# POWER_SUPPLY.net
KiCad netlist of a schematic drawn in Altium Designer
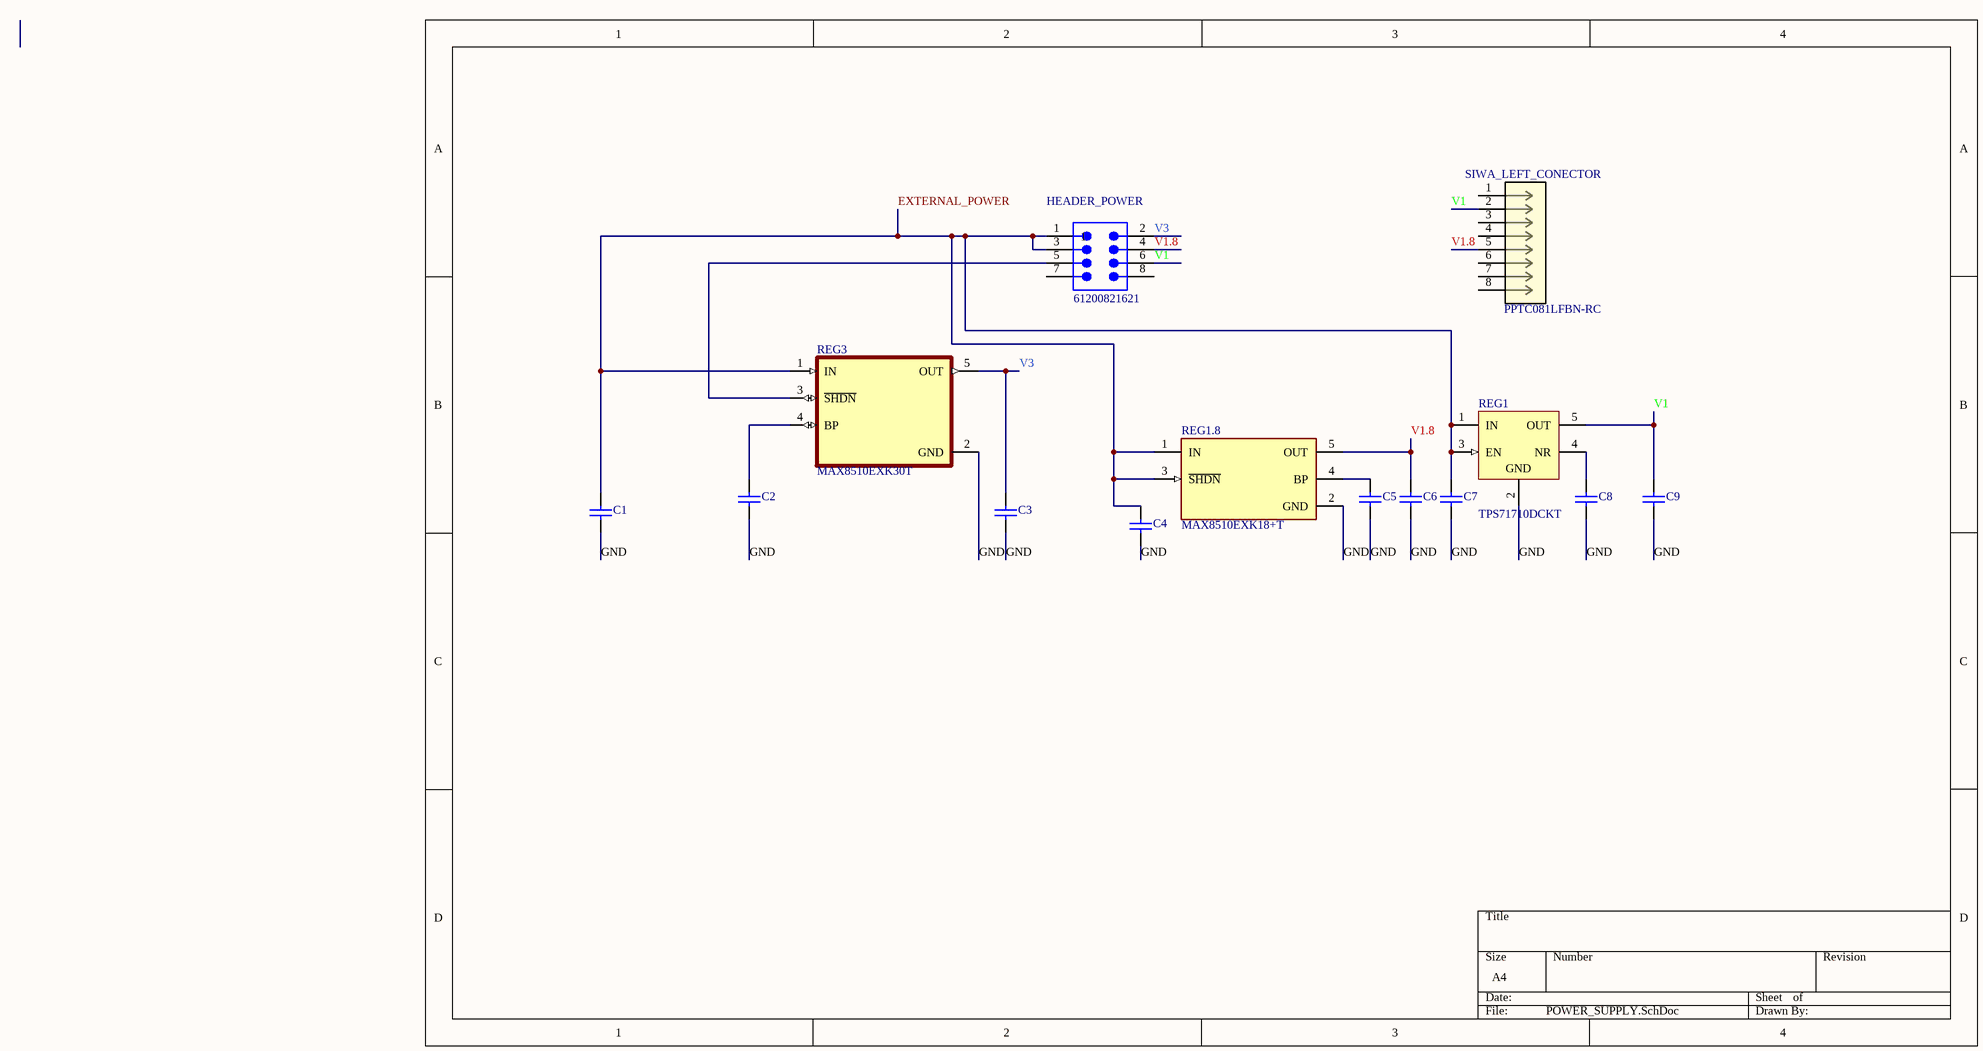
[diagram p0: POWER_SUPPLY.SchDoc]

(export (version "E")
  (design (tool "Eeschema 10.0.6"))
  (components
    (comp (ref "C1")
      (value "VJ0603Y102KXJAC")
      (footprint "CAPC1608X92X38ML15T08")
      (fields (field (name "MANUFACTURER") "Vitramon"))
      (libsource (lib "Altium Content Vault") (part "CAP"))
    )
    (comp (ref "C2")
      (value "VJ0603Y102KXJAC")
      (footprint "CAPC1608X92X38ML15T08")
      (fields (field (name "MANUFACTURER") "Vitramon"))
      (libsource (lib "Altium Content Vault") (part "CAP"))
    )
    (comp (ref "C3")
      (value "VJ0603Y102KXJAC")
      (footprint "CAPC1608X92X38ML15T08")
      (fields (field (name "MANUFACTURER") "Vitramon"))
      (libsource (lib "Altium Content Vault") (part "CAP"))
    )
    (comp (ref "C4")
      (value "VJ0603Y102KXJAC")
      (footprint "CAPC1608X92X38ML15T08")
      (fields (field (name "MANUFACTURER") "Vitramon"))
      (libsource (lib "Altium Content Vault") (part "CAP"))
    )
    (comp (ref "C5")
      (value "VJ0603Y102KXJAC")
      (footprint "CAPC1608X92X38ML15T08")
      (fields (field (name "MANUFACTURER") "Vitramon"))
      (libsource (lib "Altium Content Vault") (part "CAP"))
    )
    (comp (ref "C6")
      (value "VJ0603Y102KXJAC")
      (footprint "CAPC1608X92X38ML15T08")
      (fields (field (name "MANUFACTURER") "Vitramon"))
      (libsource (lib "Altium Content Vault") (part "CAP"))
    )
    (comp (ref "C7")
      (value "VJ0603Y102KXJAC")
      (footprint "CAPC1608X92X38ML15T08")
      (fields (field (name "MANUFACTURER") "Vitramon"))
      (libsource (lib "Altium Content Vault") (part "CAP"))
    )
    (comp (ref "C8")
      (value "VJ0603Y102KXJAC")
      (footprint "CAPC1608X92X38ML15T08")
      (fields (field (name "MANUFACTURER") "Vitramon"))
      (libsource (lib "Altium Content Vault") (part "CAP"))
    )
    (comp (ref "C9")
      (value "VJ0603Y102KXJAC")
      (footprint "CAPC1608X92X38ML15T08")
      (fields (field (name "MANUFACTURER") "Vitramon"))
      (libsource (lib "Altium Content Vault") (part "CAP"))
    )
    (comp (ref "HEADER_POWER")
      (value "61200821621")
      (footprint "61200821621")
      (description "Wr-bhd; 2.54MM Pitch 8 Way 2 Row Shrouded Straight Pcb Header, Surface Mount")
      (libsource (lib "Altium Content Vault") (part "Header_Male_2R_08P"))
    )
    (comp (ref "REG1")
      (value "TPS71710DCKT")
      (footprint "DCK0005A_M")
      (fields (field (name "MANUFACTURER") "Texas Instruments"))
      (libsource (lib "Altium Content Vault") (part "TI-TPS79NXX-YYSOT5"))
    )
    (comp (ref "REG1.8")
      (value "MAX8510EXK18+T")
      (footprint "FP-X5-1-MFG")
      (description "IC REG LINEAR 1.8V 120MA SC70-5")
      (libsource (lib "Altium Content Vault") (part "355d6218c957986cfc1b3588039a240"))
    )
    (comp (ref "REG3")
      (value "MAX8510EXK30T")
      (footprint "SOT65P210X110-5N")
      (description "DoÄŸrusal Voltaj RegÃ¼latÃ¶rÃ¼ IC Pozitif Sabit 1 Ã‡Ä±kÄ±ÅŸ 120mA SC-70-5")
      (fields (field (name "MF") "Maxim Integrated Products") (field (name "MP") "MAX8510EXK30+T"))
      (libsource (lib "MAX8510EXK30T") (part "MAX8510EXK30T"))
    )
    (comp (ref "SIWA_LEFT_CONECTOR")
      (value "PPTC081LFBN-RC")
      (footprint "CONN_PPTC081LFBN-RC_SUL")
      (description "Description")
      (fields (field (name "COPYRIGHT") "Copyright (C) 2026 Ultra Librarian. All rights reserved."))
      (libsource (lib "PPTC081LFBN-RC") (part "PPTC081LFBN-RC"))
    )
  )
  (nets
    (net (code "1") (name "/EXTERNAL_POWER") (class "Default")
      (node (ref "C1") (pin "2") (pinfunction "2_2") (pintype "passive"))
      (node (ref "C4") (pin "2") (pinfunction "2_2") (pintype "passive"))
      (node (ref "C7") (pin "2") (pinfunction "2_2") (pintype "passive"))
      (node (ref "HEADER_POWER") (pin "1") (pinfunction "1_1") (pintype "passive"))
      (node (ref "HEADER_POWER") (pin "3") (pinfunction "3_3") (pintype "passive"))
      (node (ref "REG1") (pin "1") (pinfunction "IN_1") (pintype "power_in"))
      (node (ref "REG1") (pin "3") (pinfunction "EN_3") (pintype "input"))
      (node (ref "REG1.8") (pin "1") (pinfunction "IN_1") (pintype "power_in"))
      (node (ref "REG1.8") (pin "3") (pinfunction "~{SHDN}_3") (pintype "input"))
      (node (ref "REG3") (pin "1") (pinfunction "IN_1") (pintype "input"))
    )
    (net (code "2") (name "/GND") (class "Default")
      (node (ref "C1") (pin "1") (pinfunction "1_1") (pintype "passive"))
      (node (ref "C2") (pin "1") (pinfunction "1_1") (pintype "passive"))
      (node (ref "C3") (pin "1") (pinfunction "1_1") (pintype "passive"))
      (node (ref "C4") (pin "1") (pinfunction "1_1") (pintype "passive"))
      (node (ref "C5") (pin "1") (pinfunction "1_1") (pintype "passive"))
      (node (ref "C6") (pin "1") (pinfunction "1_1") (pintype "passive"))
      (node (ref "C7") (pin "1") (pinfunction "1_1") (pintype "passive"))
      (node (ref "C8") (pin "1") (pinfunction "1_1") (pintype "passive"))
      (node (ref "C9") (pin "1") (pinfunction "1_1") (pintype "passive"))
      (node (ref "REG1") (pin "2") (pinfunction "GND_2") (pintype "power_in"))
      (node (ref "REG1.8") (pin "2") (pinfunction "GND_2") (pintype "power_in"))
      (node (ref "REG3") (pin "2") (pinfunction "GND_2") (pintype "power_in"))
    )
    (net (code "3") (name "/V1") (class "Default")
      (node (ref "C9") (pin "2") (pinfunction "2_2") (pintype "passive"))
      (node (ref "HEADER_POWER") (pin "6") (pinfunction "6_6") (pintype "passive"))
      (node (ref "REG1") (pin "5") (pinfunction "OUT_5") (pintype "power_in"))
      (node (ref "SIWA_LEFT_CONECTOR") (pin "2") (pinfunction "2_2") (pintype "passive"))
    )
    (net (code "4") (name "/V1.8") (class "Default")
      (node (ref "C6") (pin "2") (pinfunction "2_2") (pintype "passive"))
      (node (ref "HEADER_POWER") (pin "4") (pinfunction "4_4") (pintype "passive"))
      (node (ref "REG1.8") (pin "5") (pinfunction "OUT_5") (pintype "power_in"))
      (node (ref "SIWA_LEFT_CONECTOR") (pin "5") (pinfunction "5_5") (pintype "passive"))
    )
    (net (code "5") (name "/V3") (class "Default")
      (node (ref "C3") (pin "2") (pinfunction "2_2") (pintype "passive"))
      (node (ref "HEADER_POWER") (pin "2") (pinfunction "2_2") (pintype "passive"))
      (node (ref "REG3") (pin "5") (pinfunction "OUT_5") (pintype "output"))
    )
    (net (code "6") (name "Net-(REG1-NR)") (class "Default")
      (node (ref "C8") (pin "2") (pinfunction "2_2") (pintype "passive"))
      (node (ref "REG1") (pin "4") (pinfunction "NR_4") (pintype "passive"))
    )
    (net (code "7") (name "Net-(REG1.8-BP)") (class "Default")
      (node (ref "C5") (pin "2") (pinfunction "2_2") (pintype "passive"))
      (node (ref "REG1.8") (pin "4") (pinfunction "BP_4") (pintype "passive"))
    )
    (net (code "8") (name "Net-(REG3-BP)") (class "Default")
      (node (ref "C2") (pin "2") (pinfunction "2_2") (pintype "passive"))
      (node (ref "REG3") (pin "4") (pinfunction "BP_4") (pintype "bidirectional"))
    )
    (net (code "9") (name "Net-(REG3-~{SHDN})") (class "Default")
      (node (ref "HEADER_POWER") (pin "5") (pinfunction "5_5") (pintype "passive"))
      (node (ref "REG3") (pin "3") (pinfunction "~{SHDN}_3") (pintype "bidirectional"))
    )
    (net (code "10") (name "unconnected-(HEADER_POWER-Pad7)") (class "Default")
      (node (ref "HEADER_POWER") (pin "7") (pinfunction "7_7") (pintype "passive"))
    )
    (net (code "11") (name "unconnected-(HEADER_POWER-Pad8)") (class "Default")
      (node (ref "HEADER_POWER") (pin "8") (pinfunction "8_8") (pintype "passive"))
    )
    (net (code "12") (name "unconnected-(SIWA_LEFT_CONECTOR-Pad1)") (class "Default")
      (node (ref "SIWA_LEFT_CONECTOR") (pin "1") (pinfunction "1_1") (pintype "passive"))
    )
    (net (code "13") (name "unconnected-(SIWA_LEFT_CONECTOR-Pad3)") (class "Default")
      (node (ref "SIWA_LEFT_CONECTOR") (pin "3") (pinfunction "3_3") (pintype "passive"))
    )
    (net (code "14") (name "unconnected-(SIWA_LEFT_CONECTOR-Pad4)") (class "Default")
      (node (ref "SIWA_LEFT_CONECTOR") (pin "4") (pinfunction "4_4") (pintype "passive"))
    )
    (net (code "15") (name "unconnected-(SIWA_LEFT_CONECTOR-Pad6)") (class "Default")
      (node (ref "SIWA_LEFT_CONECTOR") (pin "6") (pinfunction "6_6") (pintype "passive"))
    )
    (net (code "16") (name "unconnected-(SIWA_LEFT_CONECTOR-Pad7)") (class "Default")
      (node (ref "SIWA_LEFT_CONECTOR") (pin "7") (pinfunction "7_7") (pintype "passive"))
    )
    (net (code "17") (name "unconnected-(SIWA_LEFT_CONECTOR-Pad8)") (class "Default")
      (node (ref "SIWA_LEFT_CONECTOR") (pin "8") (pinfunction "8_8") (pintype "passive"))
    )
  )
)
